# ProPrj_ATC_PTT_v1_2026-08-08.net
KiCad netlist of a schematic drawn in EasyEDA Pro
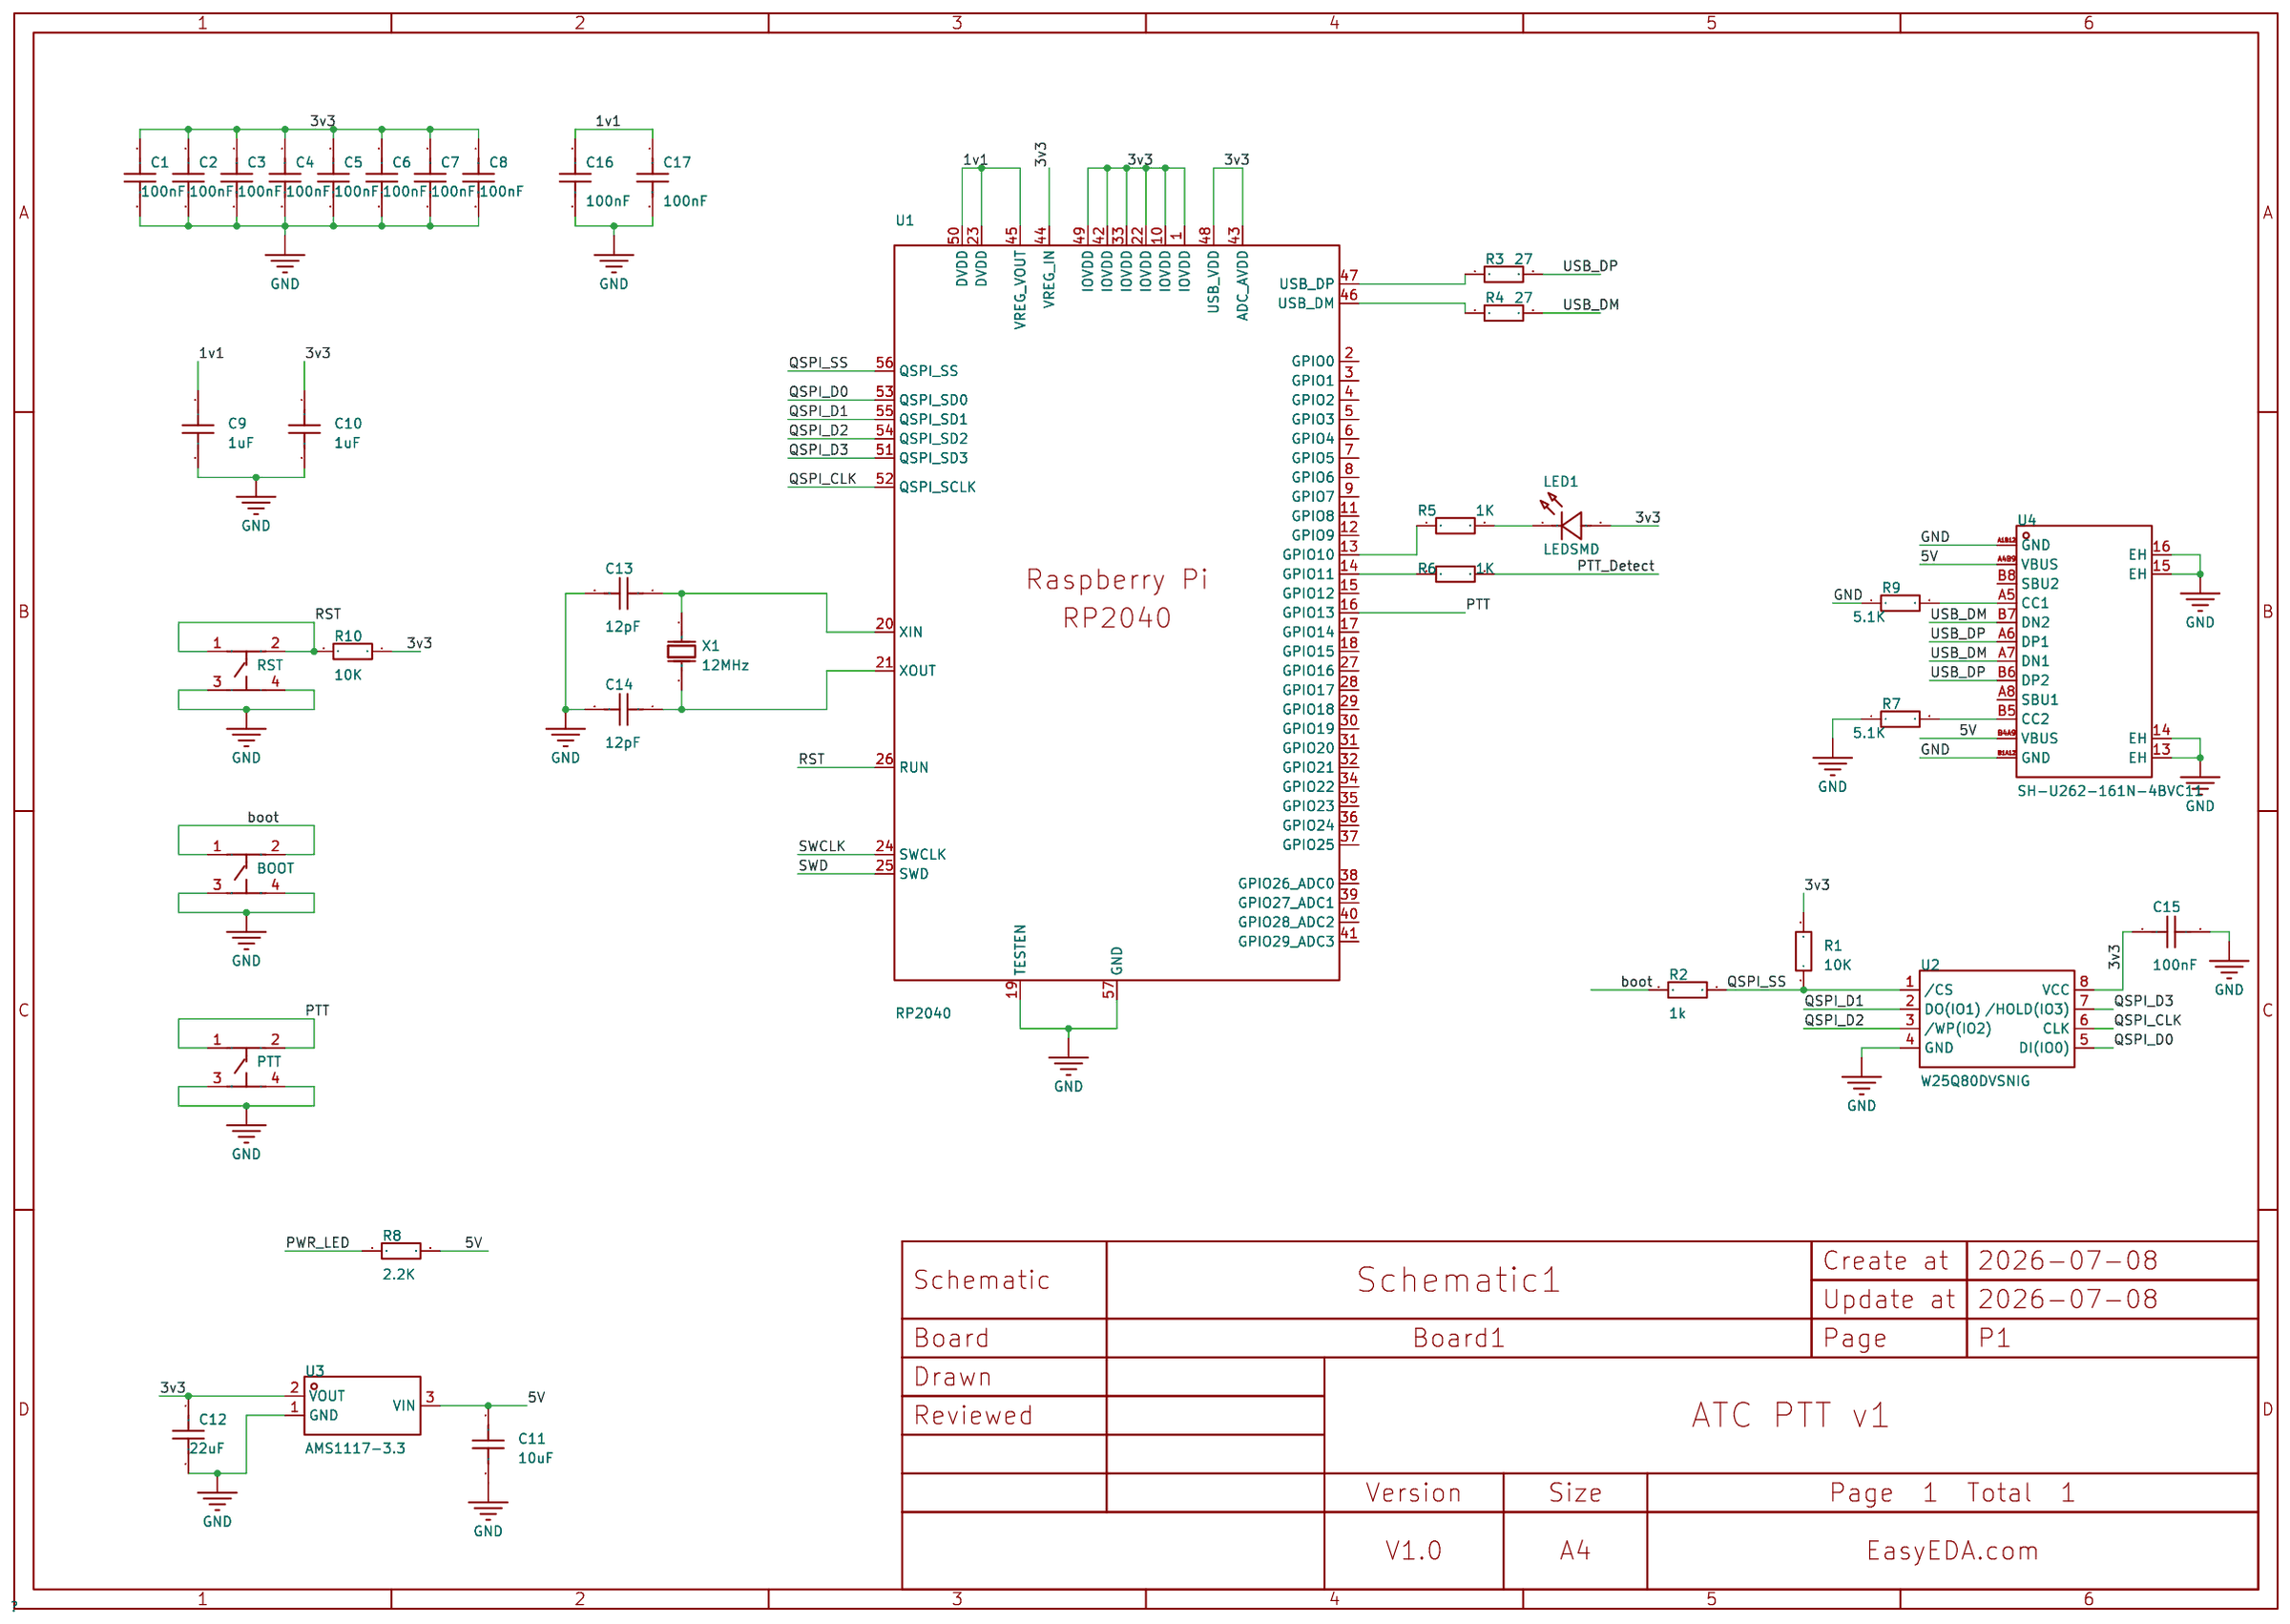
[diagram p0: schematic sheet]

(export (version "E")
  (design (tool "Eeschema 10.0.6"))
  (components
    (comp (ref "BOOT")
      (value "TSD003B06018A03")
      (footprint "easyedapro:SW-SMD_4P-L6.0-W6.0-P4.50-LS8.6")
      (fields (field (name "Manufacturer") "BZCN(博众电气)"))
      (libsource (lib "easyedapro") (part "TSD003B06018A03"))
    )
    (comp (ref "C1")
      (value "100nF")
      (footprint "easyedapro:C0603")
      (libsource (lib "easyedapro") (part "CAP"))
    )
    (comp (ref "C2")
      (value "100nF")
      (footprint "easyedapro:C0603")
      (libsource (lib "easyedapro") (part "CAP"))
    )
    (comp (ref "C3")
      (value "100nF")
      (footprint "easyedapro:C0603")
      (libsource (lib "easyedapro") (part "CAP"))
    )
    (comp (ref "C4")
      (value "100nF")
      (footprint "easyedapro:C0603")
      (libsource (lib "easyedapro") (part "CAP"))
    )
    (comp (ref "C5")
      (value "100nF")
      (footprint "easyedapro:C0603")
      (libsource (lib "easyedapro") (part "CAP"))
    )
    (comp (ref "C6")
      (value "100nF")
      (footprint "easyedapro:C0603")
      (libsource (lib "easyedapro") (part "CAP"))
    )
    (comp (ref "C7")
      (value "100nF")
      (footprint "easyedapro:C0603")
      (libsource (lib "easyedapro") (part "CAP"))
    )
    (comp (ref "C8")
      (value "100nF")
      (footprint "easyedapro:C0603")
      (libsource (lib "easyedapro") (part "CAP"))
    )
    (comp (ref "C9") (value "1uF") (footprint "easyedapro:C0603") (libsource (lib "easyedapro") (part "CAP")))
    (comp (ref "C10")
      (value "1uF")
      (footprint "easyedapro:C0603")
      (libsource (lib "easyedapro") (part "CAP"))
    )
    (comp (ref "C11")
      (value "10uF")
      (footprint "easyedapro:C0603")
      (libsource (lib "easyedapro") (part "CAP"))
    )
    (comp (ref "C12")
      (value "22uF")
      (footprint "easyedapro:C0603")
      (libsource (lib "easyedapro") (part "CAP"))
    )
    (comp (ref "C13")
      (value "12pF")
      (footprint "easyedapro:C0603")
      (libsource (lib "easyedapro") (part "CAP"))
    )
    (comp (ref "C14")
      (value "12pF")
      (footprint "easyedapro:C0603")
      (libsource (lib "easyedapro") (part "CAP"))
    )
    (comp (ref "C15")
      (value "100nF")
      (footprint "easyedapro:C0603")
      (libsource (lib "easyedapro") (part "CAP"))
    )
    (comp (ref "C16")
      (value "100nF")
      (footprint "easyedapro:C0603")
      (libsource (lib "easyedapro") (part "CAP"))
    )
    (comp (ref "C17")
      (value "100nF")
      (footprint "easyedapro:C0603")
      (libsource (lib "easyedapro") (part "CAP"))
    )
    (comp (ref "LED1")
      (value "LEDSMD")
      (footprint "easyedapro:LED0805-RD_YELLOW")
      (fields (field (name "Manufacturer") "YONGYUTAI(永裕泰)"))
      (libsource (lib "easyedapro") (part "YLED0805Y"))
    )
    (comp (ref "PTT")
      (value "TSD003B06018A03")
      (footprint "easyedapro:SW-SMD_4P-L6.0-W6.0-P4.50-LS8.6")
      (fields (field (name "Manufacturer") "BZCN(博众电气)"))
      (libsource (lib "easyedapro") (part "TSD003B06018A03"))
    )
    (comp (ref "R1") (value "10K") (footprint "easyedapro:R0603") (libsource (lib "easyedapro") (part "Res")))
    (comp (ref "R2") (value "1k") (footprint "easyedapro:R0603") (libsource (lib "easyedapro") (part "Res")))
    (comp (ref "R3") (value "27") (footprint "easyedapro:R0603") (libsource (lib "easyedapro") (part "Res")))
    (comp (ref "R4") (value "27") (footprint "easyedapro:R0603") (libsource (lib "easyedapro") (part "Res")))
    (comp (ref "R5") (value "1K") (footprint "easyedapro:R0603") (libsource (lib "easyedapro") (part "Res")))
    (comp (ref "R6") (value "1K") (footprint "easyedapro:R0603") (libsource (lib "easyedapro") (part "Res")))
    (comp (ref "R7")
      (value "5.1K")
      (footprint "easyedapro:R0603")
      (libsource (lib "easyedapro") (part "Res"))
    )
    (comp (ref "R8")
      (value "2.2K")
      (footprint "easyedapro:R0603")
      (libsource (lib "easyedapro") (part "Res"))
    )
    (comp (ref "R9")
      (value "5.1K")
      (footprint "easyedapro:R0603")
      (libsource (lib "easyedapro") (part "Res"))
    )
    (comp (ref "R10")
      (value "10K")
      (footprint "easyedapro:R0603")
      (libsource (lib "easyedapro") (part "Res"))
    )
    (comp (ref "RST")
      (value "TSD003B06018A03")
      (footprint "easyedapro:SW-SMD_4P-L6.0-W6.0-P4.50-LS8.6")
      (fields (field (name "Manufacturer") "BZCN(博众电气)"))
      (libsource (lib "easyedapro") (part "TSD003B06018A03"))
    )
    (comp (ref "U1")
      (value "RP2040")
      (footprint "easyedapro:LQFN-56_L7.0-W7.0-P0.4-EP")
      (fields (field (name "Manufacturer") "Raspberry Pi(树莓派)"))
      (libsource (lib "easyedapro") (part "RP2040"))
    )
    (comp (ref "U2")
      (value "W25Q80DVSNIG")
      (fields (field (name "Manufacturer") "Winbond(华邦)"))
      (libsource (lib "easyedapro") (part "W25Q80DVSNIG_1"))
    )
    (comp (ref "U3")
      (value "AMS1117-3.3")
      (footprint "easyedapro:SOT-223-3_L6.5-W3.4-P2.30-LS7.0-BR-1")
      (fields (field (name "Manufacturer") "晶扬电子"))
      (libsource (lib "easyedapro") (part "AMS1117-3.3_C22459274"))
    )
    (comp (ref "U4")
      (value "SH-U262-161N-4BVC11")
      (footprint "easyedapro:USB-3.1-SMD_U262-161N-4BVC11")
      (fields (field (name "Manufacturer") "SHOU HAN(首韩)"))
      (libsource (lib "easyedapro") (part "SH-U262-161N-4BVC11"))
    )
    (comp (ref "X1")
      (value "12MHz")
      (footprint "easyedapro:HC-49S_L11.4-W4.8")
      (fields (field (name "Manufacturer Part") "X49SM12MSD2SC") (field (name "Manufacturer") "YXC(扬兴晶振)"))
      (libsource (lib "easyedapro") (part "X49SM12MSD2SC"))
    )
  )
  (nets
    (net (code "1") (name "/1v1") (class "Default")
      (node (ref "C16") (pin "1") (pinfunction "1_1") (pintype "input"))
      (node (ref "C17") (pin "1") (pinfunction "1_1") (pintype "input"))
      (node (ref "C9") (pin "1") (pinfunction "1_1") (pintype "input"))
      (node (ref "U1") (pin "23") (pinfunction "DVDD_23") (pintype "bidirectional"))
      (node (ref "U1") (pin "45") (pinfunction "VREG_VOUT_45") (pintype "bidirectional"))
      (node (ref "U1") (pin "50") (pinfunction "DVDD_50") (pintype "bidirectional"))
    )
    (net (code "2") (name "/3v3") (class "Default")
      (node (ref "C1") (pin "1") (pinfunction "1_1") (pintype "input"))
      (node (ref "C10") (pin "1") (pinfunction "1_1") (pintype "input"))
      (node (ref "C12") (pin "1") (pinfunction "1_1") (pintype "input"))
      (node (ref "C15") (pin "2") (pinfunction "2_2") (pintype "input"))
      (node (ref "C2") (pin "1") (pinfunction "1_1") (pintype "input"))
      (node (ref "C3") (pin "1") (pinfunction "1_1") (pintype "input"))
      (node (ref "C4") (pin "1") (pinfunction "1_1") (pintype "input"))
      (node (ref "C5") (pin "1") (pinfunction "1_1") (pintype "input"))
      (node (ref "C6") (pin "1") (pinfunction "1_1") (pintype "input"))
      (node (ref "C7") (pin "1") (pinfunction "1_1") (pintype "input"))
      (node (ref "C8") (pin "1") (pinfunction "1_1") (pintype "input"))
      (node (ref "LED1") (pin "2") (pinfunction "A_2") (pintype "unspecified"))
      (node (ref "R1") (pin "2") (pinfunction "2_2") (pintype "input"))
      (node (ref "R10") (pin "1") (pinfunction "1_1") (pintype "input"))
      (node (ref "U1") (pin "1") (pinfunction "IOVDD_1") (pintype "bidirectional"))
      (node (ref "U1") (pin "10") (pinfunction "IOVDD_10") (pintype "bidirectional"))
      (node (ref "U1") (pin "22") (pinfunction "IOVDD_22") (pintype "bidirectional"))
      (node (ref "U1") (pin "33") (pinfunction "IOVDD_33") (pintype "bidirectional"))
      (node (ref "U1") (pin "42") (pinfunction "IOVDD_42") (pintype "bidirectional"))
      (node (ref "U1") (pin "43") (pinfunction "ADC_AVDD_43") (pintype "bidirectional"))
      (node (ref "U1") (pin "44") (pinfunction "VREG_IN_44") (pintype "bidirectional"))
      (node (ref "U1") (pin "48") (pinfunction "USB_VDD_48") (pintype "bidirectional"))
      (node (ref "U1") (pin "49") (pinfunction "IOVDD_49") (pintype "bidirectional"))
      (node (ref "U2") (pin "8") (pinfunction "VCC_8") (pintype "unspecified"))
      (node (ref "U3") (pin "2") (pinfunction "VOUT_2") (pintype "unspecified"))
    )
    (net (code "3") (name "/5V") (class "Default")
      (node (ref "C11") (pin "1") (pinfunction "1_1") (pintype "input"))
      (node (ref "R8") (pin "2") (pinfunction "2_2") (pintype "input"))
      (node (ref "U3") (pin "3") (pinfunction "VIN_3") (pintype "unspecified"))
      (node (ref "U4") (pin "A4B9") (pinfunction "VBUS_A4B9") (pintype "unspecified"))
      (node (ref "U4") (pin "B4A9") (pinfunction "VBUS_B4A9") (pintype "unspecified"))
    )
    (net (code "4") (name "/PTT") (class "Default")
      (node (ref "PTT") (pin "1") (pinfunction "1_1") (pintype "unspecified"))
      (node (ref "PTT") (pin "2") (pinfunction "2_2") (pintype "unspecified"))
      (node (ref "U1") (pin "16") (pinfunction "GPIO13_16") (pintype "bidirectional"))
    )
    (net (code "5") (name "/PTT_Detect") (class "Default")
      (node (ref "R6") (pin "2") (pinfunction "2_2") (pintype "input"))
    )
    (net (code "6") (name "/PWR_LED") (class "Default")
      (node (ref "R8") (pin "1") (pinfunction "1_1") (pintype "input"))
    )
    (net (code "7") (name "/QSPI_CLK") (class "Default")
      (node (ref "U1") (pin "52") (pinfunction "QSPI_SCLK_52") (pintype "output"))
      (node (ref "U2") (pin "6") (pinfunction "CLK_6") (pintype "unspecified"))
    )
    (net (code "8") (name "/QSPI_D0") (class "Default")
      (node (ref "U1") (pin "53") (pinfunction "QSPI_SD0_53") (pintype "bidirectional"))
      (node (ref "U2") (pin "5") (pinfunction "DI(IO0)_5") (pintype "unspecified"))
    )
    (net (code "9") (name "/QSPI_D1") (class "Default")
      (node (ref "U1") (pin "55") (pinfunction "QSPI_SD1_55") (pintype "bidirectional"))
      (node (ref "U2") (pin "2") (pinfunction "DO(IO1)_2") (pintype "unspecified"))
    )
    (net (code "10") (name "/QSPI_D2") (class "Default")
      (node (ref "U1") (pin "54") (pinfunction "QSPI_SD2_54") (pintype "bidirectional"))
      (node (ref "U2") (pin "3") (pinfunction "/WP(IO2)_3") (pintype "unspecified"))
    )
    (net (code "11") (name "/QSPI_D3") (class "Default")
      (node (ref "U1") (pin "51") (pinfunction "QSPI_SD3_51") (pintype "bidirectional"))
      (node (ref "U2") (pin "7") (pinfunction "/HOLD(IO3)_7") (pintype "unspecified"))
    )
    (net (code "12") (name "/QSPI_SS") (class "Default")
      (node (ref "R1") (pin "1") (pinfunction "1_1") (pintype "input"))
      (node (ref "R2") (pin "1") (pinfunction "1_1") (pintype "input"))
      (node (ref "U1") (pin "56") (pinfunction "QSPI_SS_56") (pintype "bidirectional"))
      (node (ref "U2") (pin "1") (pinfunction "/CS_1") (pintype "unspecified"))
    )
    (net (code "13") (name "/RST") (class "Default")
      (node (ref "R10") (pin "2") (pinfunction "2_2") (pintype "input"))
      (node (ref "RST") (pin "1") (pinfunction "1_1") (pintype "unspecified"))
      (node (ref "RST") (pin "2") (pinfunction "2_2") (pintype "unspecified"))
      (node (ref "U1") (pin "26") (pinfunction "RUN_26") (pintype "input"))
    )
    (net (code "14") (name "/SWCLK") (class "Default")
      (node (ref "U1") (pin "24") (pinfunction "SWCLK_24") (pintype "output"))
    )
    (net (code "15") (name "/SWD") (class "Default")
      (node (ref "U1") (pin "25") (pinfunction "SWD_25") (pintype "bidirectional"))
    )
    (net (code "16") (name "/USB_DM") (class "Default")
      (node (ref "R4") (pin "2") (pinfunction "2_2") (pintype "input"))
      (node (ref "U4") (pin "A7") (pinfunction "DN1_A7") (pintype "unspecified"))
      (node (ref "U4") (pin "B7") (pinfunction "DN2_B7") (pintype "unspecified"))
    )
    (net (code "17") (name "/USB_DP") (class "Default")
      (node (ref "R3") (pin "2") (pinfunction "2_2") (pintype "input"))
      (node (ref "U4") (pin "A6") (pinfunction "DP1_A6") (pintype "unspecified"))
      (node (ref "U4") (pin "B6") (pinfunction "DP2_B6") (pintype "unspecified"))
    )
    (net (code "18") (name "/boot") (class "Default")
      (node (ref "BOOT") (pin "1") (pinfunction "1_1") (pintype "unspecified"))
      (node (ref "BOOT") (pin "2") (pinfunction "2_2") (pintype "unspecified"))
      (node (ref "R2") (pin "2") (pinfunction "2_2") (pintype "input"))
    )
    (net (code "19") (name "GND") (class "Default")
      (node (ref "BOOT") (pin "3") (pinfunction "3_3") (pintype "unspecified"))
      (node (ref "BOOT") (pin "4") (pinfunction "4_4") (pintype "unspecified"))
      (node (ref "C1") (pin "2") (pinfunction "2_2") (pintype "input"))
      (node (ref "C10") (pin "2") (pinfunction "2_2") (pintype "input"))
      (node (ref "C11") (pin "2") (pinfunction "2_2") (pintype "input"))
      (node (ref "C12") (pin "2") (pinfunction "2_2") (pintype "input"))
      (node (ref "C13") (pin "2") (pinfunction "2_2") (pintype "input"))
      (node (ref "C14") (pin "2") (pinfunction "2_2") (pintype "input"))
      (node (ref "C15") (pin "1") (pinfunction "1_1") (pintype "input"))
      (node (ref "C16") (pin "2") (pinfunction "2_2") (pintype "input"))
      (node (ref "C17") (pin "2") (pinfunction "2_2") (pintype "input"))
      (node (ref "C2") (pin "2") (pinfunction "2_2") (pintype "input"))
      (node (ref "C3") (pin "2") (pinfunction "2_2") (pintype "input"))
      (node (ref "C4") (pin "2") (pinfunction "2_2") (pintype "input"))
      (node (ref "C5") (pin "2") (pinfunction "2_2") (pintype "input"))
      (node (ref "C6") (pin "2") (pinfunction "2_2") (pintype "input"))
      (node (ref "C7") (pin "2") (pinfunction "2_2") (pintype "input"))
      (node (ref "C8") (pin "2") (pinfunction "2_2") (pintype "input"))
      (node (ref "C9") (pin "2") (pinfunction "2_2") (pintype "input"))
      (node (ref "PTT") (pin "3") (pinfunction "3_3") (pintype "unspecified"))
      (node (ref "PTT") (pin "4") (pinfunction "4_4") (pintype "unspecified"))
      (node (ref "R7") (pin "1") (pinfunction "1_1") (pintype "input"))
      (node (ref "R9") (pin "1") (pinfunction "1_1") (pintype "input"))
      (node (ref "RST") (pin "3") (pinfunction "3_3") (pintype "unspecified"))
      (node (ref "RST") (pin "4") (pinfunction "4_4") (pintype "unspecified"))
      (node (ref "U1") (pin "19") (pinfunction "TESTEN_19") (pintype "unspecified"))
      (node (ref "U1") (pin "57") (pinfunction "GND_57") (pintype "bidirectional"))
      (node (ref "U2") (pin "4") (pinfunction "GND_4") (pintype "unspecified"))
      (node (ref "U3") (pin "1") (pinfunction "GND_1") (pintype "unspecified"))
      (node (ref "U4") (pin "13") (pinfunction "EH_13") (pintype "unspecified"))
      (node (ref "U4") (pin "14") (pinfunction "EH_14") (pintype "unspecified"))
      (node (ref "U4") (pin "15") (pinfunction "EH_15") (pintype "unspecified"))
      (node (ref "U4") (pin "16") (pinfunction "EH_16") (pintype "unspecified"))
      (node (ref "U4") (pin "A1B12") (pinfunction "GND_A1B12") (pintype "unspecified"))
      (node (ref "U4") (pin "B1A12") (pinfunction "GND_B1A12") (pintype "unspecified"))
    )
    (net (code "20") (name "Net-(LED1-K)") (class "Default")
      (node (ref "LED1") (pin "1") (pinfunction "K_1") (pintype "unspecified"))
      (node (ref "R5") (pin "2") (pinfunction "2_2") (pintype "input"))
    )
    (net (code "21") (name "Net-(U1-GPIO10)") (class "Default")
      (node (ref "R5") (pin "1") (pinfunction "1_1") (pintype "input"))
      (node (ref "U1") (pin "13") (pinfunction "GPIO10_13") (pintype "bidirectional"))
    )
    (net (code "22") (name "Net-(U1-GPIO11)") (class "Default")
      (node (ref "R6") (pin "1") (pinfunction "1_1") (pintype "input"))
      (node (ref "U1") (pin "14") (pinfunction "GPIO11_14") (pintype "bidirectional"))
    )
    (net (code "23") (name "Net-(U1-USB_DM)") (class "Default")
      (node (ref "R4") (pin "1") (pinfunction "1_1") (pintype "input"))
      (node (ref "U1") (pin "46") (pinfunction "USB_DM_46") (pintype "bidirectional"))
    )
    (net (code "24") (name "Net-(U1-USB_DP)") (class "Default")
      (node (ref "R3") (pin "1") (pinfunction "1_1") (pintype "input"))
      (node (ref "U1") (pin "47") (pinfunction "USB_DP_47") (pintype "bidirectional"))
    )
    (net (code "25") (name "Net-(U1-XIN)") (class "Default")
      (node (ref "C13") (pin "1") (pinfunction "1_1") (pintype "input"))
      (node (ref "U1") (pin "20") (pinfunction "XIN_20") (pintype "input"))
      (node (ref "X1") (pin "1") (pinfunction "OSC1_1") (pintype "input"))
    )
    (net (code "26") (name "Net-(U1-XOUT)") (class "Default")
      (node (ref "C14") (pin "1") (pinfunction "1_1") (pintype "input"))
      (node (ref "U1") (pin "21") (pinfunction "XOUT_21") (pintype "unspecified"))
      (node (ref "X1") (pin "2") (pinfunction "OSC2_2") (pintype "input"))
    )
    (net (code "27") (name "Net-(U4-CC1)") (class "Default")
      (node (ref "R9") (pin "2") (pinfunction "2_2") (pintype "input"))
      (node (ref "U4") (pin "A5") (pinfunction "CC1_A5") (pintype "unspecified"))
    )
    (net (code "28") (name "Net-(U4-CC2)") (class "Default")
      (node (ref "R7") (pin "2") (pinfunction "2_2") (pintype "input"))
      (node (ref "U4") (pin "B5") (pinfunction "CC2_B5") (pintype "unspecified"))
    )
    (net (code "29") (name "unconnected-(U1-GPIO0-Pad2)") (class "Default")
      (node (ref "U1") (pin "2") (pinfunction "GPIO0_2") (pintype "bidirectional"))
    )
    (net (code "30") (name "unconnected-(U1-GPIO1-Pad3)") (class "Default")
      (node (ref "U1") (pin "3") (pinfunction "GPIO1_3") (pintype "bidirectional"))
    )
    (net (code "31") (name "unconnected-(U1-GPIO2-Pad4)") (class "Default")
      (node (ref "U1") (pin "4") (pinfunction "GPIO2_4") (pintype "bidirectional"))
    )
    (net (code "32") (name "unconnected-(U1-GPIO3-Pad5)") (class "Default")
      (node (ref "U1") (pin "5") (pinfunction "GPIO3_5") (pintype "bidirectional"))
    )
    (net (code "33") (name "unconnected-(U1-GPIO4-Pad6)") (class "Default")
      (node (ref "U1") (pin "6") (pinfunction "GPIO4_6") (pintype "bidirectional"))
    )
    (net (code "34") (name "unconnected-(U1-GPIO5-Pad7)") (class "Default")
      (node (ref "U1") (pin "7") (pinfunction "GPIO5_7") (pintype "bidirectional"))
    )
    (net (code "35") (name "unconnected-(U1-GPIO6-Pad8)") (class "Default")
      (node (ref "U1") (pin "8") (pinfunction "GPIO6_8") (pintype "bidirectional"))
    )
    (net (code "36") (name "unconnected-(U1-GPIO7-Pad9)") (class "Default")
      (node (ref "U1") (pin "9") (pinfunction "GPIO7_9") (pintype "bidirectional"))
    )
    (net (code "37") (name "unconnected-(U1-GPIO8-Pad11)") (class "Default")
      (node (ref "U1") (pin "11") (pinfunction "GPIO8_11") (pintype "bidirectional"))
    )
    (net (code "38") (name "unconnected-(U1-GPIO9-Pad12)") (class "Default")
      (node (ref "U1") (pin "12") (pinfunction "GPIO9_12") (pintype "bidirectional"))
    )
    (net (code "39") (name "unconnected-(U1-GPIO12-Pad15)") (class "Default")
      (node (ref "U1") (pin "15") (pinfunction "GPIO12_15") (pintype "bidirectional"))
    )
    (net (code "40") (name "unconnected-(U1-GPIO14-Pad17)") (class "Default")
      (node (ref "U1") (pin "17") (pinfunction "GPIO14_17") (pintype "bidirectional"))
    )
    (net (code "41") (name "unconnected-(U1-GPIO15-Pad18)") (class "Default")
      (node (ref "U1") (pin "18") (pinfunction "GPIO15_18") (pintype "bidirectional"))
    )
    (net (code "42") (name "unconnected-(U1-GPIO16-Pad27)") (class "Default")
      (node (ref "U1") (pin "27") (pinfunction "GPIO16_27") (pintype "bidirectional"))
    )
    (net (code "43") (name "unconnected-(U1-GPIO17-Pad28)") (class "Default")
      (node (ref "U1") (pin "28") (pinfunction "GPIO17_28") (pintype "bidirectional"))
    )
    (net (code "44") (name "unconnected-(U1-GPIO18-Pad29)") (class "Default")
      (node (ref "U1") (pin "29") (pinfunction "GPIO18_29") (pintype "bidirectional"))
    )
    (net (code "45") (name "unconnected-(U1-GPIO19-Pad30)") (class "Default")
      (node (ref "U1") (pin "30") (pinfunction "GPIO19_30") (pintype "bidirectional"))
    )
    (net (code "46") (name "unconnected-(U1-GPIO20-Pad31)") (class "Default")
      (node (ref "U1") (pin "31") (pinfunction "GPIO20_31") (pintype "bidirectional"))
    )
    (net (code "47") (name "unconnected-(U1-GPIO21-Pad32)") (class "Default")
      (node (ref "U1") (pin "32") (pinfunction "GPIO21_32") (pintype "bidirectional"))
    )
    (net (code "48") (name "unconnected-(U1-GPIO22-Pad34)") (class "Default")
      (node (ref "U1") (pin "34") (pinfunction "GPIO22_34") (pintype "bidirectional"))
    )
    (net (code "49") (name "unconnected-(U1-GPIO23-Pad35)") (class "Default")
      (node (ref "U1") (pin "35") (pinfunction "GPIO23_35") (pintype "bidirectional"))
    )
    (net (code "50") (name "unconnected-(U1-GPIO24-Pad36)") (class "Default")
      (node (ref "U1") (pin "36") (pinfunction "GPIO24_36") (pintype "bidirectional"))
    )
    (net (code "51") (name "unconnected-(U1-GPIO25-Pad37)") (class "Default")
      (node (ref "U1") (pin "37") (pinfunction "GPIO25_37") (pintype "bidirectional"))
    )
    (net (code "52") (name "unconnected-(U1-GPIO26_ADC0-Pad38)") (class "Default")
      (node (ref "U1") (pin "38") (pinfunction "GPIO26_ADC0_38") (pintype "bidirectional"))
    )
    (net (code "53") (name "unconnected-(U1-GPIO27_ADC1-Pad39)") (class "Default")
      (node (ref "U1") (pin "39") (pinfunction "GPIO27_ADC1_39") (pintype "bidirectional"))
    )
    (net (code "54") (name "unconnected-(U1-GPIO28_ADC2-Pad40)") (class "Default")
      (node (ref "U1") (pin "40") (pinfunction "GPIO28_ADC2_40") (pintype "bidirectional"))
    )
    (net (code "55") (name "unconnected-(U1-GPIO29_ADC3-Pad41)") (class "Default")
      (node (ref "U1") (pin "41") (pinfunction "GPIO29_ADC3_41") (pintype "bidirectional"))
    )
    (net (code "56") (name "unconnected-(U4-SBU1-PadA8)") (class "Default")
      (node (ref "U4") (pin "A8") (pinfunction "SBU1_A8") (pintype "unspecified"))
    )
    (net (code "57") (name "unconnected-(U4-SBU2-PadB8)") (class "Default")
      (node (ref "U4") (pin "B8") (pinfunction "SBU2_B8") (pintype "unspecified"))
    )
  )
)
